# LED_s_Pedal.net
KiCad netlist of a schematic drawn in Altium Designer
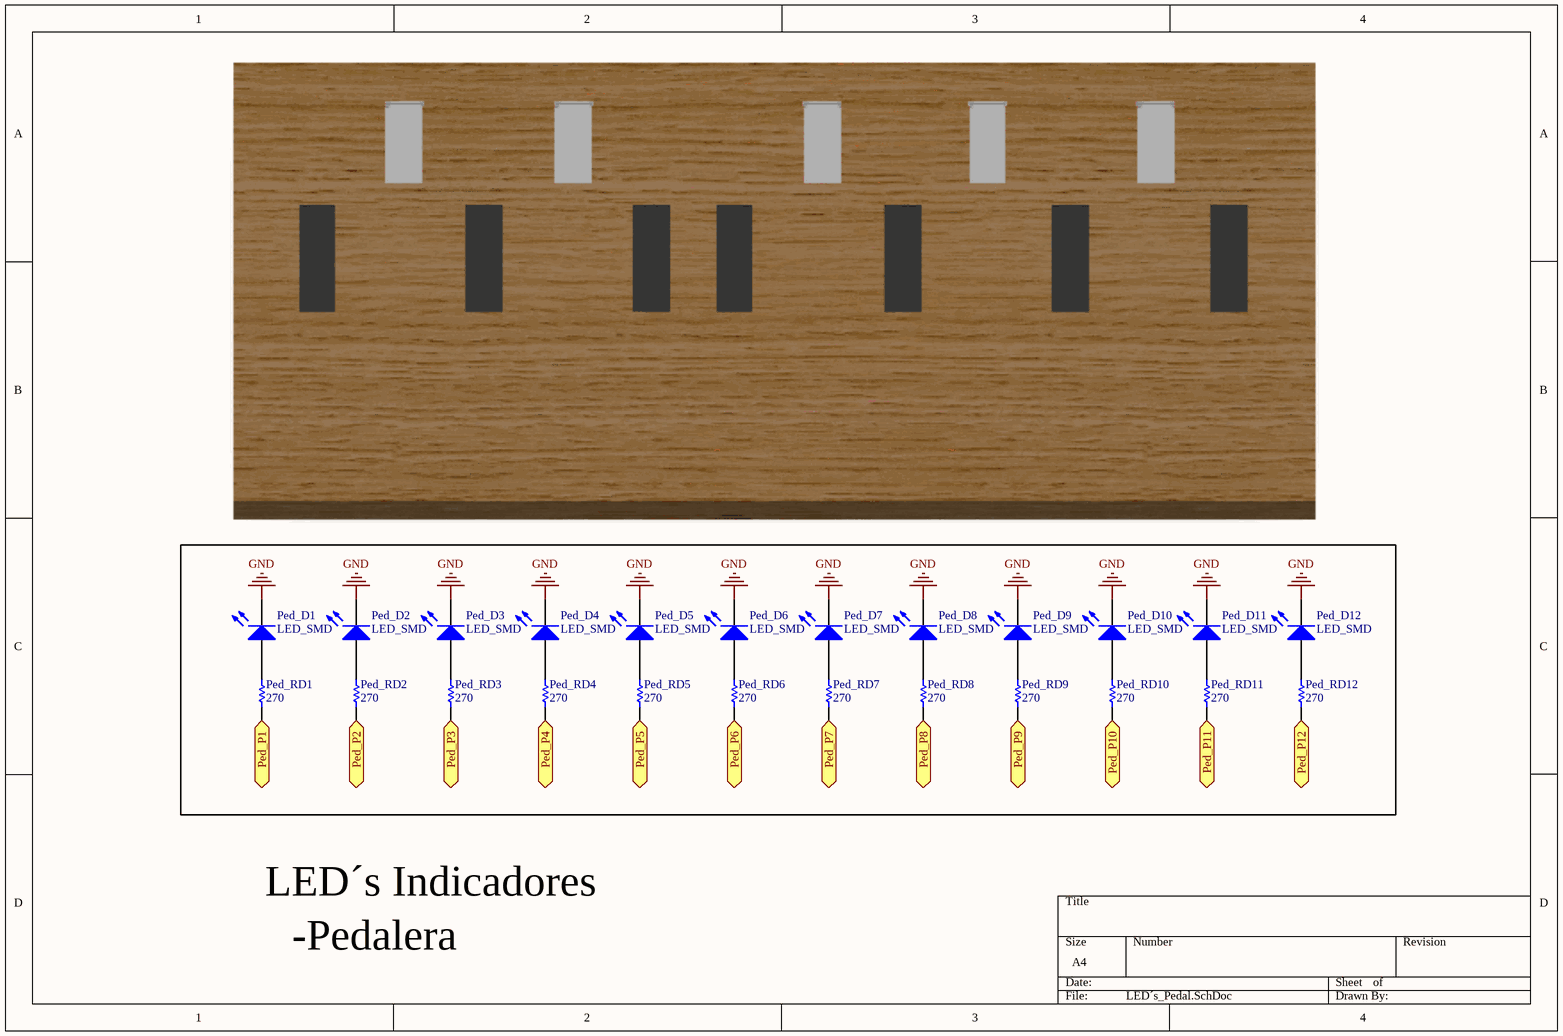
[diagram p0: LED´s_Pedal.SchDoc]

(export (version "E")
  (design (tool "Eeschema 10.0.6"))
  (components
    (comp (ref "Ped_D1")
      (value "LED_SMD")
      (footprint "0805")
      (description "LED SMD")
      (fields (field (name "PUBLISHER") "Altium Limited"))
      (libsource (lib "Libreria_Organo") (part "LED_SMD"))
    )
    (comp (ref "Ped_D2")
      (value "LED_SMD")
      (footprint "0805")
      (description "LED SMD")
      (fields (field (name "PUBLISHER") "Altium Limited"))
      (libsource (lib "Libreria_Organo") (part "LED_SMD"))
    )
    (comp (ref "Ped_D3")
      (value "LED_SMD")
      (footprint "0805")
      (description "LED SMD")
      (fields (field (name "PUBLISHER") "Altium Limited"))
      (libsource (lib "Libreria_Organo") (part "LED_SMD"))
    )
    (comp (ref "Ped_D4")
      (value "LED_SMD")
      (footprint "0805")
      (description "LED SMD")
      (fields (field (name "PUBLISHER") "Altium Limited"))
      (libsource (lib "Libreria_Organo") (part "LED_SMD"))
    )
    (comp (ref "Ped_D5")
      (value "LED_SMD")
      (footprint "0805")
      (description "LED SMD")
      (fields (field (name "PUBLISHER") "Altium Limited"))
      (libsource (lib "Libreria_Organo") (part "LED_SMD"))
    )
    (comp (ref "Ped_D6")
      (value "LED_SMD")
      (footprint "0805")
      (description "LED SMD")
      (fields (field (name "PUBLISHER") "Altium Limited"))
      (libsource (lib "Libreria_Organo") (part "LED_SMD"))
    )
    (comp (ref "Ped_D7")
      (value "LED_SMD")
      (footprint "0805")
      (description "LED SMD")
      (fields (field (name "PUBLISHER") "Altium Limited"))
      (libsource (lib "Libreria_Organo") (part "LED_SMD"))
    )
    (comp (ref "Ped_D8")
      (value "LED_SMD")
      (footprint "0805")
      (description "LED SMD")
      (fields (field (name "PUBLISHER") "Altium Limited"))
      (libsource (lib "Libreria_Organo") (part "LED_SMD"))
    )
    (comp (ref "Ped_D9")
      (value "LED_SMD")
      (footprint "0805")
      (description "LED SMD")
      (fields (field (name "PUBLISHER") "Altium Limited"))
      (libsource (lib "Libreria_Organo") (part "LED_SMD"))
    )
    (comp (ref "Ped_D10")
      (value "LED_SMD")
      (footprint "0805")
      (description "LED SMD")
      (fields (field (name "PUBLISHER") "Altium Limited"))
      (libsource (lib "Libreria_Organo") (part "LED_SMD"))
    )
    (comp (ref "Ped_D11")
      (value "LED_SMD")
      (footprint "0805")
      (description "LED SMD")
      (fields (field (name "PUBLISHER") "Altium Limited"))
      (libsource (lib "Libreria_Organo") (part "LED_SMD"))
    )
    (comp (ref "Ped_D12")
      (value "LED_SMD")
      (footprint "0805")
      (description "LED SMD")
      (fields (field (name "PUBLISHER") "Altium Limited"))
      (libsource (lib "Libreria_Organo") (part "LED_SMD"))
    )
    (comp (ref "Ped_RD1")
      (value "270")
      (footprint "0805 Chip Res")
      (description "Res Chip 0805")
      (fields (field (name "PUBLISHER") "Altium Limited"))
      (libsource (lib "Libreria_Organo") (part "Resistencia"))
    )
    (comp (ref "Ped_RD2")
      (value "270")
      (footprint "0805 Chip Res")
      (description "Res Chip 0805")
      (fields (field (name "PUBLISHER") "Altium Limited"))
      (libsource (lib "Libreria_Organo") (part "Resistencia"))
    )
    (comp (ref "Ped_RD3")
      (value "270")
      (footprint "0805 Chip Res")
      (description "Res Chip 0805")
      (fields (field (name "PUBLISHER") "Altium Limited"))
      (libsource (lib "Libreria_Organo") (part "Resistencia"))
    )
    (comp (ref "Ped_RD4")
      (value "270")
      (footprint "0805 Chip Res")
      (description "Res Chip 0805")
      (fields (field (name "PUBLISHER") "Altium Limited"))
      (libsource (lib "Libreria_Organo") (part "Resistencia"))
    )
    (comp (ref "Ped_RD5")
      (value "270")
      (footprint "0805 Chip Res")
      (description "Res Chip 0805")
      (fields (field (name "PUBLISHER") "Altium Limited"))
      (libsource (lib "Libreria_Organo") (part "Resistencia"))
    )
    (comp (ref "Ped_RD6")
      (value "270")
      (footprint "0805 Chip Res")
      (description "Res Chip 0805")
      (fields (field (name "PUBLISHER") "Altium Limited"))
      (libsource (lib "Libreria_Organo") (part "Resistencia"))
    )
    (comp (ref "Ped_RD7")
      (value "270")
      (footprint "0805 Chip Res")
      (description "Res Chip 0805")
      (fields (field (name "PUBLISHER") "Altium Limited"))
      (libsource (lib "Libreria_Organo") (part "Resistencia"))
    )
    (comp (ref "Ped_RD8")
      (value "270")
      (footprint "0805 Chip Res")
      (description "Res Chip 0805")
      (fields (field (name "PUBLISHER") "Altium Limited"))
      (libsource (lib "Libreria_Organo") (part "Resistencia"))
    )
    (comp (ref "Ped_RD9")
      (value "270")
      (footprint "0805 Chip Res")
      (description "Res Chip 0805")
      (fields (field (name "PUBLISHER") "Altium Limited"))
      (libsource (lib "Libreria_Organo") (part "Resistencia"))
    )
    (comp (ref "Ped_RD10")
      (value "270")
      (footprint "0805 Chip Res")
      (description "Res Chip 0805")
      (fields (field (name "PUBLISHER") "Altium Limited"))
      (libsource (lib "Libreria_Organo") (part "Resistencia"))
    )
    (comp (ref "Ped_RD11")
      (value "270")
      (footprint "0805 Chip Res")
      (description "Res Chip 0805")
      (fields (field (name "PUBLISHER") "Altium Limited"))
      (libsource (lib "Libreria_Organo") (part "Resistencia"))
    )
    (comp (ref "Ped_RD12")
      (value "270")
      (footprint "0805 Chip Res")
      (description "Res Chip 0805")
      (fields (field (name "PUBLISHER") "Altium Limited"))
      (libsource (lib "Libreria_Organo") (part "Resistencia"))
    )
  )
  (nets
    (net (code "1") (name "/Ped_P1") (class "Default")
      (node (ref "Ped_RD1") (pin "1") (pinfunction "1_1") (pintype "passive"))
    )
    (net (code "2") (name "/Ped_P2") (class "Default")
      (node (ref "Ped_RD2") (pin "1") (pinfunction "1_1") (pintype "passive"))
    )
    (net (code "3") (name "/Ped_P3") (class "Default")
      (node (ref "Ped_RD3") (pin "1") (pinfunction "1_1") (pintype "passive"))
    )
    (net (code "4") (name "/Ped_P4") (class "Default")
      (node (ref "Ped_RD4") (pin "1") (pinfunction "1_1") (pintype "passive"))
    )
    (net (code "5") (name "/Ped_P5") (class "Default")
      (node (ref "Ped_RD5") (pin "1") (pinfunction "1_1") (pintype "passive"))
    )
    (net (code "6") (name "/Ped_P6") (class "Default")
      (node (ref "Ped_RD6") (pin "1") (pinfunction "1_1") (pintype "passive"))
    )
    (net (code "7") (name "/Ped_P7") (class "Default")
      (node (ref "Ped_RD7") (pin "1") (pinfunction "1_1") (pintype "passive"))
    )
    (net (code "8") (name "/Ped_P8") (class "Default")
      (node (ref "Ped_RD8") (pin "1") (pinfunction "1_1") (pintype "passive"))
    )
    (net (code "9") (name "/Ped_P9") (class "Default")
      (node (ref "Ped_RD9") (pin "1") (pinfunction "1_1") (pintype "passive"))
    )
    (net (code "10") (name "/Ped_P10") (class "Default")
      (node (ref "Ped_RD10") (pin "1") (pinfunction "1_1") (pintype "passive"))
    )
    (net (code "11") (name "/Ped_P11") (class "Default")
      (node (ref "Ped_RD11") (pin "1") (pinfunction "1_1") (pintype "passive"))
    )
    (net (code "12") (name "/Ped_P12") (class "Default")
      (node (ref "Ped_RD12") (pin "1") (pinfunction "1_1") (pintype "passive"))
    )
    (net (code "13") (name "GND") (class "Default")
      (node (ref "Ped_D1") (pin "2") (pinfunction "K_2") (pintype "passive"))
      (node (ref "Ped_D10") (pin "2") (pinfunction "K_2") (pintype "passive"))
      (node (ref "Ped_D11") (pin "2") (pinfunction "K_2") (pintype "passive"))
      (node (ref "Ped_D12") (pin "2") (pinfunction "K_2") (pintype "passive"))
      (node (ref "Ped_D2") (pin "2") (pinfunction "K_2") (pintype "passive"))
      (node (ref "Ped_D3") (pin "2") (pinfunction "K_2") (pintype "passive"))
      (node (ref "Ped_D4") (pin "2") (pinfunction "K_2") (pintype "passive"))
      (node (ref "Ped_D5") (pin "2") (pinfunction "K_2") (pintype "passive"))
      (node (ref "Ped_D6") (pin "2") (pinfunction "K_2") (pintype "passive"))
      (node (ref "Ped_D7") (pin "2") (pinfunction "K_2") (pintype "passive"))
      (node (ref "Ped_D8") (pin "2") (pinfunction "K_2") (pintype "passive"))
      (node (ref "Ped_D9") (pin "2") (pinfunction "K_2") (pintype "passive"))
    )
    (net (code "14") (name "Net-(Ped_D1-A)") (class "Default")
      (node (ref "Ped_D1") (pin "1") (pinfunction "A_1") (pintype "passive"))
      (node (ref "Ped_RD1") (pin "2") (pinfunction "2_2") (pintype "passive"))
    )
    (net (code "15") (name "Net-(Ped_D2-A)") (class "Default")
      (node (ref "Ped_D2") (pin "1") (pinfunction "A_1") (pintype "passive"))
      (node (ref "Ped_RD2") (pin "2") (pinfunction "2_2") (pintype "passive"))
    )
    (net (code "16") (name "Net-(Ped_D3-A)") (class "Default")
      (node (ref "Ped_D3") (pin "1") (pinfunction "A_1") (pintype "passive"))
      (node (ref "Ped_RD3") (pin "2") (pinfunction "2_2") (pintype "passive"))
    )
    (net (code "17") (name "Net-(Ped_D4-A)") (class "Default")
      (node (ref "Ped_D4") (pin "1") (pinfunction "A_1") (pintype "passive"))
      (node (ref "Ped_RD4") (pin "2") (pinfunction "2_2") (pintype "passive"))
    )
    (net (code "18") (name "Net-(Ped_D5-A)") (class "Default")
      (node (ref "Ped_D5") (pin "1") (pinfunction "A_1") (pintype "passive"))
      (node (ref "Ped_RD5") (pin "2") (pinfunction "2_2") (pintype "passive"))
    )
    (net (code "19") (name "Net-(Ped_D6-A)") (class "Default")
      (node (ref "Ped_D6") (pin "1") (pinfunction "A_1") (pintype "passive"))
      (node (ref "Ped_RD6") (pin "2") (pinfunction "2_2") (pintype "passive"))
    )
    (net (code "20") (name "Net-(Ped_D7-A)") (class "Default")
      (node (ref "Ped_D7") (pin "1") (pinfunction "A_1") (pintype "passive"))
      (node (ref "Ped_RD7") (pin "2") (pinfunction "2_2") (pintype "passive"))
    )
    (net (code "21") (name "Net-(Ped_D8-A)") (class "Default")
      (node (ref "Ped_D8") (pin "1") (pinfunction "A_1") (pintype "passive"))
      (node (ref "Ped_RD8") (pin "2") (pinfunction "2_2") (pintype "passive"))
    )
    (net (code "22") (name "Net-(Ped_D9-A)") (class "Default")
      (node (ref "Ped_D9") (pin "1") (pinfunction "A_1") (pintype "passive"))
      (node (ref "Ped_RD9") (pin "2") (pinfunction "2_2") (pintype "passive"))
    )
    (net (code "23") (name "Net-(Ped_D10-A)") (class "Default")
      (node (ref "Ped_D10") (pin "1") (pinfunction "A_1") (pintype "passive"))
      (node (ref "Ped_RD10") (pin "2") (pinfunction "2_2") (pintype "passive"))
    )
    (net (code "24") (name "Net-(Ped_D11-A)") (class "Default")
      (node (ref "Ped_D11") (pin "1") (pinfunction "A_1") (pintype "passive"))
      (node (ref "Ped_RD11") (pin "2") (pinfunction "2_2") (pintype "passive"))
    )
    (net (code "25") (name "Net-(Ped_D12-A)") (class "Default")
      (node (ref "Ped_D12") (pin "1") (pinfunction "A_1") (pintype "passive"))
      (node (ref "Ped_RD12") (pin "2") (pinfunction "2_2") (pintype "passive"))
    )
  )
)
